# InterfazSensores.net
KiCad netlist of a schematic drawn in EAGLE
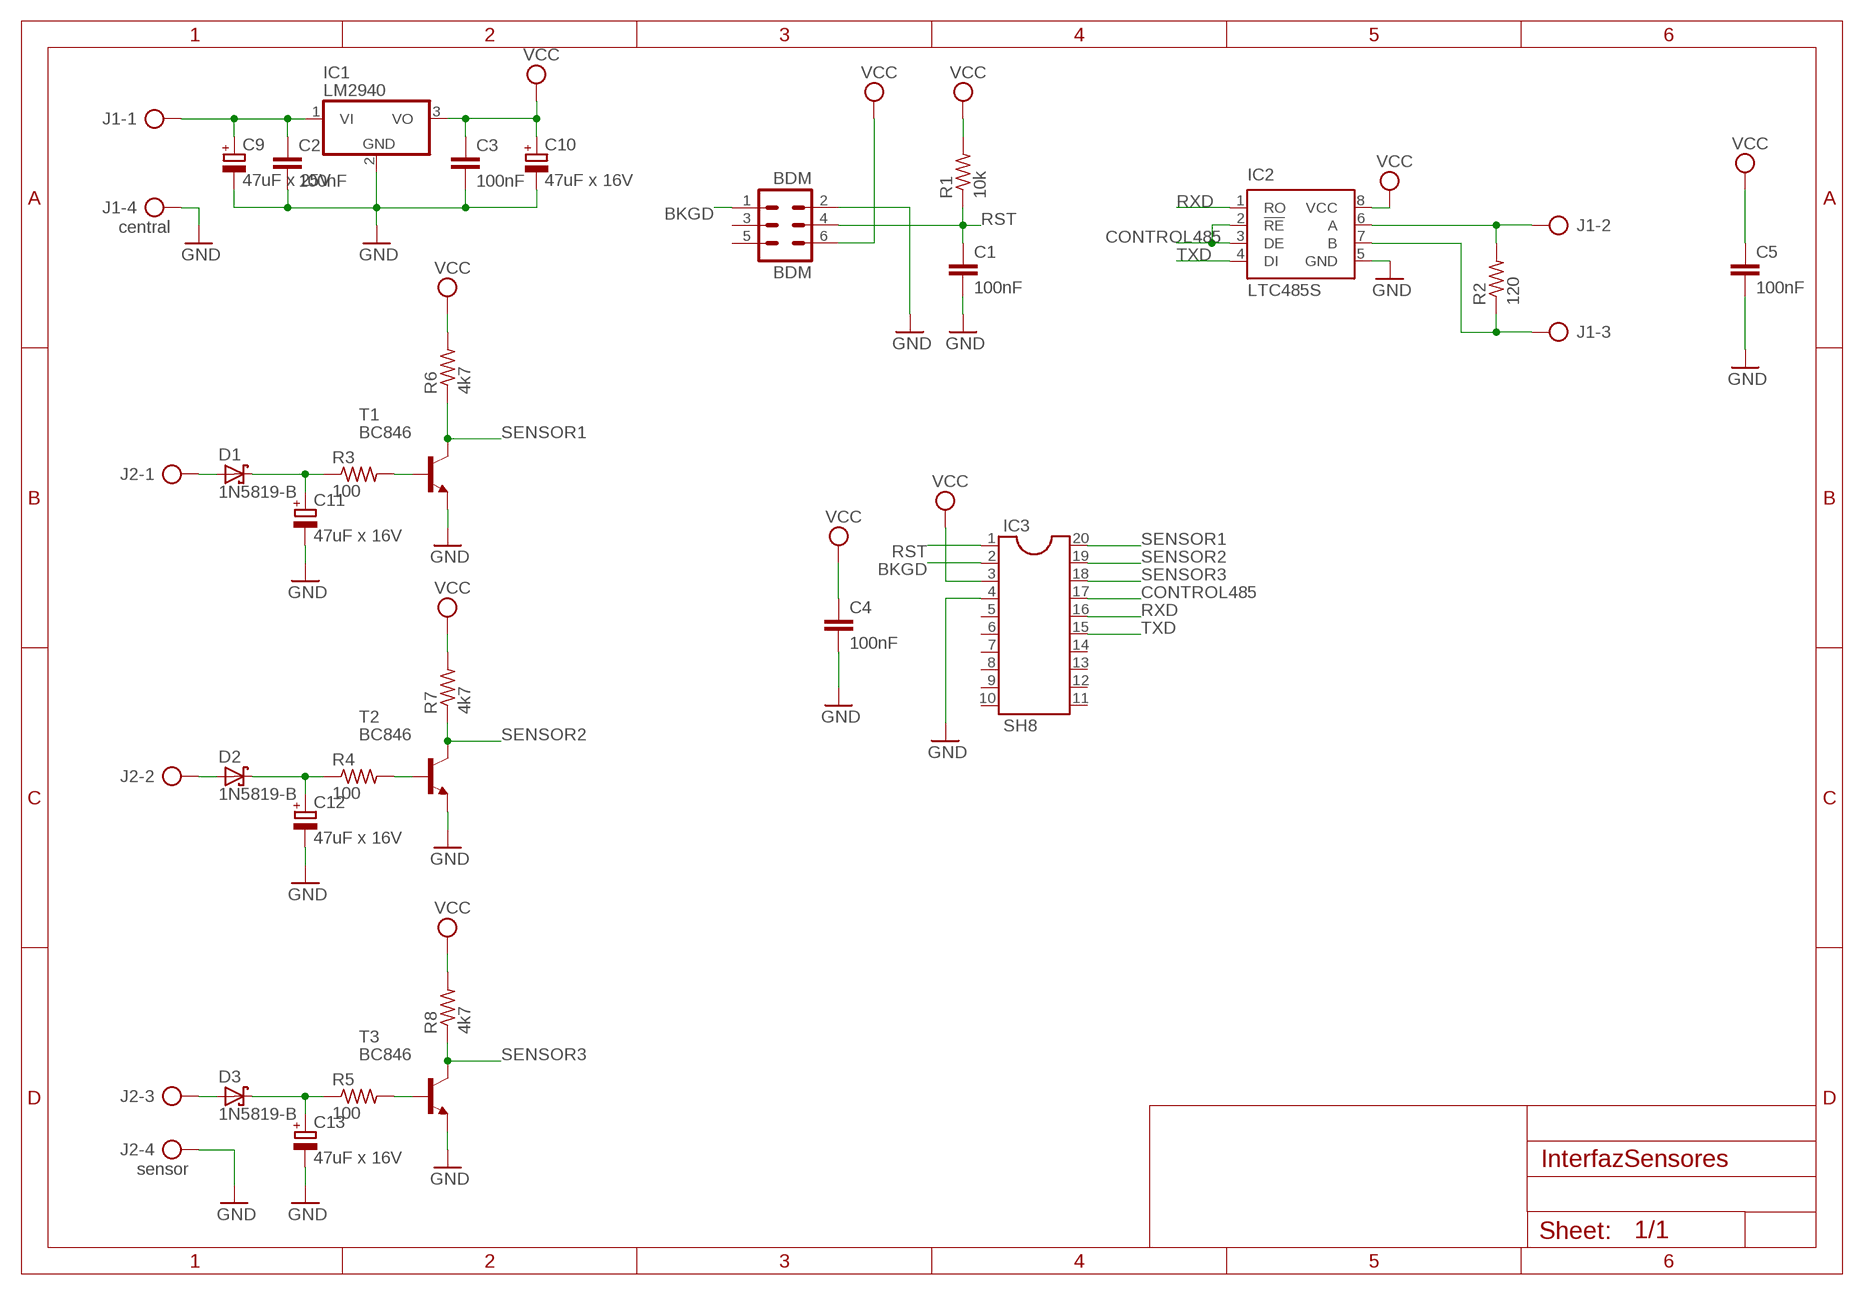
[diagram p0: schematic, sheet 1]

(export (version "E")
  (design (tool "Eeschema 10.0.6"))
  (components
    (comp (ref "BDM")
      (value "BDM")
      (footprint "eagle-import:MA03-2")
      (libsource (lib "eagle-import") (part "MA03-2"))
    )
    (comp (ref "C1")
      (value "100nF")
      (footprint "eagle-import:C0805")
      (libsource (lib "eagle-import") (part "C-EUC0805"))
    )
    (comp (ref "C2")
      (value "100nF")
      (footprint "eagle-import:C0805")
      (libsource (lib "eagle-import") (part "C-EUC0805"))
    )
    (comp (ref "C3")
      (value "100nF")
      (footprint "eagle-import:C0805")
      (libsource (lib "eagle-import") (part "C-EUC0805"))
    )
    (comp (ref "C4")
      (value "100nF")
      (footprint "eagle-import:C0805")
      (libsource (lib "eagle-import") (part "C-EUC0805"))
    )
    (comp (ref "C5")
      (value "100nF")
      (footprint "eagle-import:C0805")
      (libsource (lib "eagle-import") (part "C-EUC0805"))
    )
    (comp (ref "C9")
      (value "47uF x 25V")
      (footprint "eagle-import:E2,5-6E")
      (libsource (lib "eagle-import") (part "CPOL-EUE2,5-6E"))
    )
    (comp (ref "C10")
      (value "47uF x 16V")
      (footprint "eagle-import:E2,5-6E")
      (libsource (lib "eagle-import") (part "CPOL-EUE2,5-6E"))
    )
    (comp (ref "C11")
      (value "47uF x 16V")
      (footprint "eagle-import:E2,5-6E")
      (libsource (lib "eagle-import") (part "CPOL-EUE2,5-6E"))
    )
    (comp (ref "C12")
      (value "47uF x 16V")
      (footprint "eagle-import:E2,5-6E")
      (libsource (lib "eagle-import") (part "CPOL-EUE2,5-6E"))
    )
    (comp (ref "C13")
      (value "47uF x 16V")
      (footprint "eagle-import:E2,5-6E")
      (libsource (lib "eagle-import") (part "CPOL-EUE2,5-6E"))
    )
    (comp (ref "D1")
      (value "1N5819-B")
      (footprint "eagle-import:DO41-7.6")
      (libsource (lib "eagle-import") (part "1N5819-B"))
    )
    (comp (ref "D2")
      (value "1N5819-B")
      (footprint "eagle-import:DO41-7.6")
      (libsource (lib "eagle-import") (part "1N5819-B"))
    )
    (comp (ref "D3")
      (value "1N5819-B")
      (footprint "eagle-import:DO41-7.6")
      (libsource (lib "eagle-import") (part "1N5819-B"))
    )
    (comp (ref "IC1")
      (value "LM2940")
      (footprint "eagle-import:TO220V")
      (libsource (lib "eagle-import") (part "78TV05"))
    )
    (comp (ref "IC2")
      (value "LTC485S")
      (footprint "eagle-import:SOIC8")
      (libsource (lib "eagle-import") (part "LTC485S"))
    )
    (comp (ref "IC3")
      (value "SH8")
      (footprint "eagle-import:DIL20")
      (libsource (lib "eagle-import") (part "DIL20"))
    )
    (comp (ref "J1")
      (value "central")
      (footprint "eagle-import:AK300_4")
      (libsource (lib "eagle-import") (part "AK300/4"))
    )
    (comp (ref "J2")
      (value "sensor")
      (footprint "eagle-import:AK300_4")
      (libsource (lib "eagle-import") (part "AK300/4"))
    )
    (comp (ref "R1")
      (value "10k")
      (footprint "eagle-import:R0805")
      (libsource (lib "eagle-import") (part "R-US_R0805"))
    )
    (comp (ref "R2")
      (value "120")
      (footprint "eagle-import:R0805")
      (libsource (lib "eagle-import") (part "R-US_R0805"))
    )
    (comp (ref "R3")
      (value "100")
      (footprint "eagle-import:R0805")
      (libsource (lib "eagle-import") (part "R-US_R0805"))
    )
    (comp (ref "R4")
      (value "100")
      (footprint "eagle-import:R0805")
      (libsource (lib "eagle-import") (part "R-US_R0805"))
    )
    (comp (ref "R5")
      (value "100")
      (footprint "eagle-import:R0805")
      (libsource (lib "eagle-import") (part "R-US_R0805"))
    )
    (comp (ref "R6")
      (value "4k7")
      (footprint "eagle-import:R0805")
      (libsource (lib "eagle-import") (part "R-US_R0805"))
    )
    (comp (ref "R7")
      (value "4k7")
      (footprint "eagle-import:R0805")
      (libsource (lib "eagle-import") (part "R-US_R0805"))
    )
    (comp (ref "R8")
      (value "4k7")
      (footprint "eagle-import:R0805")
      (libsource (lib "eagle-import") (part "R-US_R0805"))
    )
    (comp (ref "T1")
      (value "BC846")
      (footprint "eagle-import:SOT23")
      (libsource (lib "eagle-import") (part "BC846"))
    )
    (comp (ref "T2")
      (value "BC846")
      (footprint "eagle-import:SOT23")
      (libsource (lib "eagle-import") (part "BC846"))
    )
    (comp (ref "T3")
      (value "BC846")
      (footprint "eagle-import:SOT23")
      (libsource (lib "eagle-import") (part "BC846"))
    )
  )
  (nets
    (net (code "1") (name "/BKGD") (class "Default")
      (node (ref "BDM") (pin "1") (pinfunction "1_1") (pintype "passive"))
      (node (ref "IC3") (pin "2") (pinfunction "2_2") (pintype "passive"))
    )
    (net (code "2") (name "/CONTROL485") (class "Default")
      (node (ref "IC2") (pin "2") (pinfunction "~{RE}_2") (pintype "input"))
      (node (ref "IC2") (pin "3") (pinfunction "DE_3") (pintype "input"))
      (node (ref "IC3") (pin "17") (pinfunction "17_17") (pintype "passive"))
    )
    (net (code "3") (name "/RST") (class "Default")
      (node (ref "BDM") (pin "4") (pinfunction "4_4") (pintype "passive"))
      (node (ref "C1") (pin "1") (pinfunction "1_1") (pintype "passive"))
      (node (ref "IC3") (pin "1") (pinfunction "1_1") (pintype "passive"))
      (node (ref "R1") (pin "1") (pinfunction "1_1") (pintype "passive"))
    )
    (net (code "4") (name "/RXD") (class "Default")
      (node (ref "IC2") (pin "1") (pinfunction "RO_1") (pintype "output"))
      (node (ref "IC3") (pin "16") (pinfunction "16_16") (pintype "passive"))
    )
    (net (code "5") (name "/SENSOR1") (class "Default")
      (node (ref "IC3") (pin "20") (pinfunction "20_20") (pintype "passive"))
      (node (ref "R6") (pin "1") (pinfunction "1_1") (pintype "passive"))
      (node (ref "T1") (pin "3") (pinfunction "C_3") (pintype "passive"))
    )
    (net (code "6") (name "/SENSOR2") (class "Default")
      (node (ref "IC3") (pin "19") (pinfunction "19_19") (pintype "passive"))
      (node (ref "R7") (pin "1") (pinfunction "1_1") (pintype "passive"))
      (node (ref "T2") (pin "3") (pinfunction "C_3") (pintype "passive"))
    )
    (net (code "7") (name "/SENSOR3") (class "Default")
      (node (ref "IC3") (pin "18") (pinfunction "18_18") (pintype "passive"))
      (node (ref "R8") (pin "1") (pinfunction "1_1") (pintype "passive"))
      (node (ref "T3") (pin "3") (pinfunction "C_3") (pintype "passive"))
    )
    (net (code "8") (name "/TXD") (class "Default")
      (node (ref "IC2") (pin "4") (pinfunction "DI_4") (pintype "input"))
      (node (ref "IC3") (pin "15") (pinfunction "15_15") (pintype "passive"))
    )
    (net (code "9") (name "GND") (class "Default")
      (node (ref "BDM") (pin "2") (pinfunction "2_2") (pintype "passive"))
      (node (ref "C1") (pin "2") (pinfunction "2_2") (pintype "passive"))
      (node (ref "C10") (pin "-") (pinfunction "-_-") (pintype "passive"))
      (node (ref "C11") (pin "-") (pinfunction "-_-") (pintype "passive"))
      (node (ref "C12") (pin "-") (pinfunction "-_-") (pintype "passive"))
      (node (ref "C13") (pin "-") (pinfunction "-_-") (pintype "passive"))
      (node (ref "C2") (pin "2") (pinfunction "2_2") (pintype "passive"))
      (node (ref "C3") (pin "2") (pinfunction "2_2") (pintype "passive"))
      (node (ref "C4") (pin "2") (pinfunction "2_2") (pintype "passive"))
      (node (ref "C5") (pin "2") (pinfunction "2_2") (pintype "passive"))
      (node (ref "C9") (pin "-") (pinfunction "-_-") (pintype "passive"))
      (node (ref "IC1") (pin "2") (pinfunction "GND_2") (pintype "passive"))
      (node (ref "IC2") (pin "5") (pinfunction "GND_5") (pintype "input"))
      (node (ref "IC3") (pin "4") (pinfunction "4_4") (pintype "passive"))
      (node (ref "J1") (pin "4") (pinfunction "KL_4") (pintype "passive"))
      (node (ref "J2") (pin "4") (pinfunction "KL_4") (pintype "passive"))
      (node (ref "T1") (pin "2") (pinfunction "E_2") (pintype "passive"))
      (node (ref "T2") (pin "2") (pinfunction "E_2") (pintype "passive"))
      (node (ref "T3") (pin "2") (pinfunction "E_2") (pintype "passive"))
    )
    (net (code "10") (name "Net-(C11-Pad+)") (class "Default")
      (node (ref "C11") (pin "+") (pinfunction "+_+") (pintype "passive"))
      (node (ref "D1") (pin "C") (pinfunction "C_C") (pintype "passive"))
      (node (ref "R3") (pin "1") (pinfunction "1_1") (pintype "passive"))
    )
    (net (code "11") (name "Net-(C12-Pad+)") (class "Default")
      (node (ref "C12") (pin "+") (pinfunction "+_+") (pintype "passive"))
      (node (ref "D2") (pin "C") (pinfunction "C_C") (pintype "passive"))
      (node (ref "R4") (pin "1") (pinfunction "1_1") (pintype "passive"))
    )
    (net (code "12") (name "Net-(C13-Pad+)") (class "Default")
      (node (ref "C13") (pin "+") (pinfunction "+_+") (pintype "passive"))
      (node (ref "D3") (pin "C") (pinfunction "C_C") (pintype "passive"))
      (node (ref "R5") (pin "1") (pinfunction "1_1") (pintype "passive"))
    )
    (net (code "13") (name "Net-(IC1-VI)") (class "Default")
      (node (ref "C2") (pin "1") (pinfunction "1_1") (pintype "passive"))
      (node (ref "C9") (pin "+") (pinfunction "+_+") (pintype "passive"))
      (node (ref "IC1") (pin "1") (pinfunction "VI_1") (pintype "input"))
      (node (ref "J1") (pin "1") (pinfunction "KL_1") (pintype "passive"))
    )
    (net (code "14") (name "Net-(IC2-A)") (class "Default")
      (node (ref "IC2") (pin "6") (pinfunction "A_6") (pintype "bidirectional"))
      (node (ref "J1") (pin "2") (pinfunction "KL_2") (pintype "passive"))
      (node (ref "R2") (pin "2") (pinfunction "2_2") (pintype "passive"))
    )
    (net (code "15") (name "Net-(IC2-B)") (class "Default")
      (node (ref "IC2") (pin "7") (pinfunction "B_7") (pintype "bidirectional"))
      (node (ref "J1") (pin "3") (pinfunction "KL_3") (pintype "passive"))
      (node (ref "R2") (pin "1") (pinfunction "1_1") (pintype "passive"))
    )
    (net (code "16") (name "Net-(J2A-KL)") (class "Default")
      (node (ref "D1") (pin "A") (pinfunction "A_A") (pintype "passive"))
      (node (ref "J2") (pin "1") (pinfunction "KL_1") (pintype "passive"))
    )
    (net (code "17") (name "Net-(J2B-KL)") (class "Default")
      (node (ref "D2") (pin "A") (pinfunction "A_A") (pintype "passive"))
      (node (ref "J2") (pin "2") (pinfunction "KL_2") (pintype "passive"))
    )
    (net (code "18") (name "Net-(J2C-KL)") (class "Default")
      (node (ref "D3") (pin "A") (pinfunction "A_A") (pintype "passive"))
      (node (ref "J2") (pin "3") (pinfunction "KL_3") (pintype "passive"))
    )
    (net (code "19") (name "Net-(T1-B)") (class "Default")
      (node (ref "R3") (pin "2") (pinfunction "2_2") (pintype "passive"))
      (node (ref "T1") (pin "1") (pinfunction "B_1") (pintype "passive"))
    )
    (net (code "20") (name "Net-(T2-B)") (class "Default")
      (node (ref "R4") (pin "2") (pinfunction "2_2") (pintype "passive"))
      (node (ref "T2") (pin "1") (pinfunction "B_1") (pintype "passive"))
    )
    (net (code "21") (name "Net-(T3-B)") (class "Default")
      (node (ref "R5") (pin "2") (pinfunction "2_2") (pintype "passive"))
      (node (ref "T3") (pin "1") (pinfunction "B_1") (pintype "passive"))
    )
    (net (code "22") (name "VCC") (class "Default")
      (node (ref "BDM") (pin "6") (pinfunction "6_6") (pintype "passive"))
      (node (ref "C10") (pin "+") (pinfunction "+_+") (pintype "passive"))
      (node (ref "C3") (pin "1") (pinfunction "1_1") (pintype "passive"))
      (node (ref "C4") (pin "1") (pinfunction "1_1") (pintype "passive"))
      (node (ref "C5") (pin "1") (pinfunction "1_1") (pintype "passive"))
      (node (ref "IC1") (pin "3") (pinfunction "VO_3") (pintype "passive"))
      (node (ref "IC2") (pin "8") (pinfunction "VCC_8") (pintype "input"))
      (node (ref "IC3") (pin "3") (pinfunction "3_3") (pintype "passive"))
      (node (ref "R1") (pin "2") (pinfunction "2_2") (pintype "passive"))
      (node (ref "R6") (pin "2") (pinfunction "2_2") (pintype "passive"))
      (node (ref "R7") (pin "2") (pinfunction "2_2") (pintype "passive"))
      (node (ref "R8") (pin "2") (pinfunction "2_2") (pintype "passive"))
    )
    (net (code "23") (name "unconnected-(BDM-Pad3)") (class "Default")
      (node (ref "BDM") (pin "3") (pinfunction "3_3") (pintype "passive"))
    )
    (net (code "24") (name "unconnected-(BDM-Pad5)") (class "Default")
      (node (ref "BDM") (pin "5") (pinfunction "5_5") (pintype "passive"))
    )
    (net (code "25") (name "unconnected-(IC3-Pad5)") (class "Default")
      (node (ref "IC3") (pin "5") (pinfunction "5_5") (pintype "passive"))
    )
    (net (code "26") (name "unconnected-(IC3-Pad6)") (class "Default")
      (node (ref "IC3") (pin "6") (pinfunction "6_6") (pintype "passive"))
    )
    (net (code "27") (name "unconnected-(IC3-Pad7)") (class "Default")
      (node (ref "IC3") (pin "7") (pinfunction "7_7") (pintype "passive"))
    )
    (net (code "28") (name "unconnected-(IC3-Pad8)") (class "Default")
      (node (ref "IC3") (pin "8") (pinfunction "8_8") (pintype "passive"))
    )
    (net (code "29") (name "unconnected-(IC3-Pad9)") (class "Default")
      (node (ref "IC3") (pin "9") (pinfunction "9_9") (pintype "passive"))
    )
    (net (code "30") (name "unconnected-(IC3-Pad10)") (class "Default")
      (node (ref "IC3") (pin "10") (pinfunction "10_10") (pintype "passive"))
    )
    (net (code "31") (name "unconnected-(IC3-Pad11)") (class "Default")
      (node (ref "IC3") (pin "11") (pinfunction "11_11") (pintype "passive"))
    )
    (net (code "32") (name "unconnected-(IC3-Pad12)") (class "Default")
      (node (ref "IC3") (pin "12") (pinfunction "12_12") (pintype "passive"))
    )
    (net (code "33") (name "unconnected-(IC3-Pad13)") (class "Default")
      (node (ref "IC3") (pin "13") (pinfunction "13_13") (pintype "passive"))
    )
    (net (code "34") (name "unconnected-(IC3-Pad14)") (class "Default")
      (node (ref "IC3") (pin "14") (pinfunction "14_14") (pintype "passive"))
    )
  )
)
